# LED.net
KiCad netlist of a schematic drawn in EasyEDA
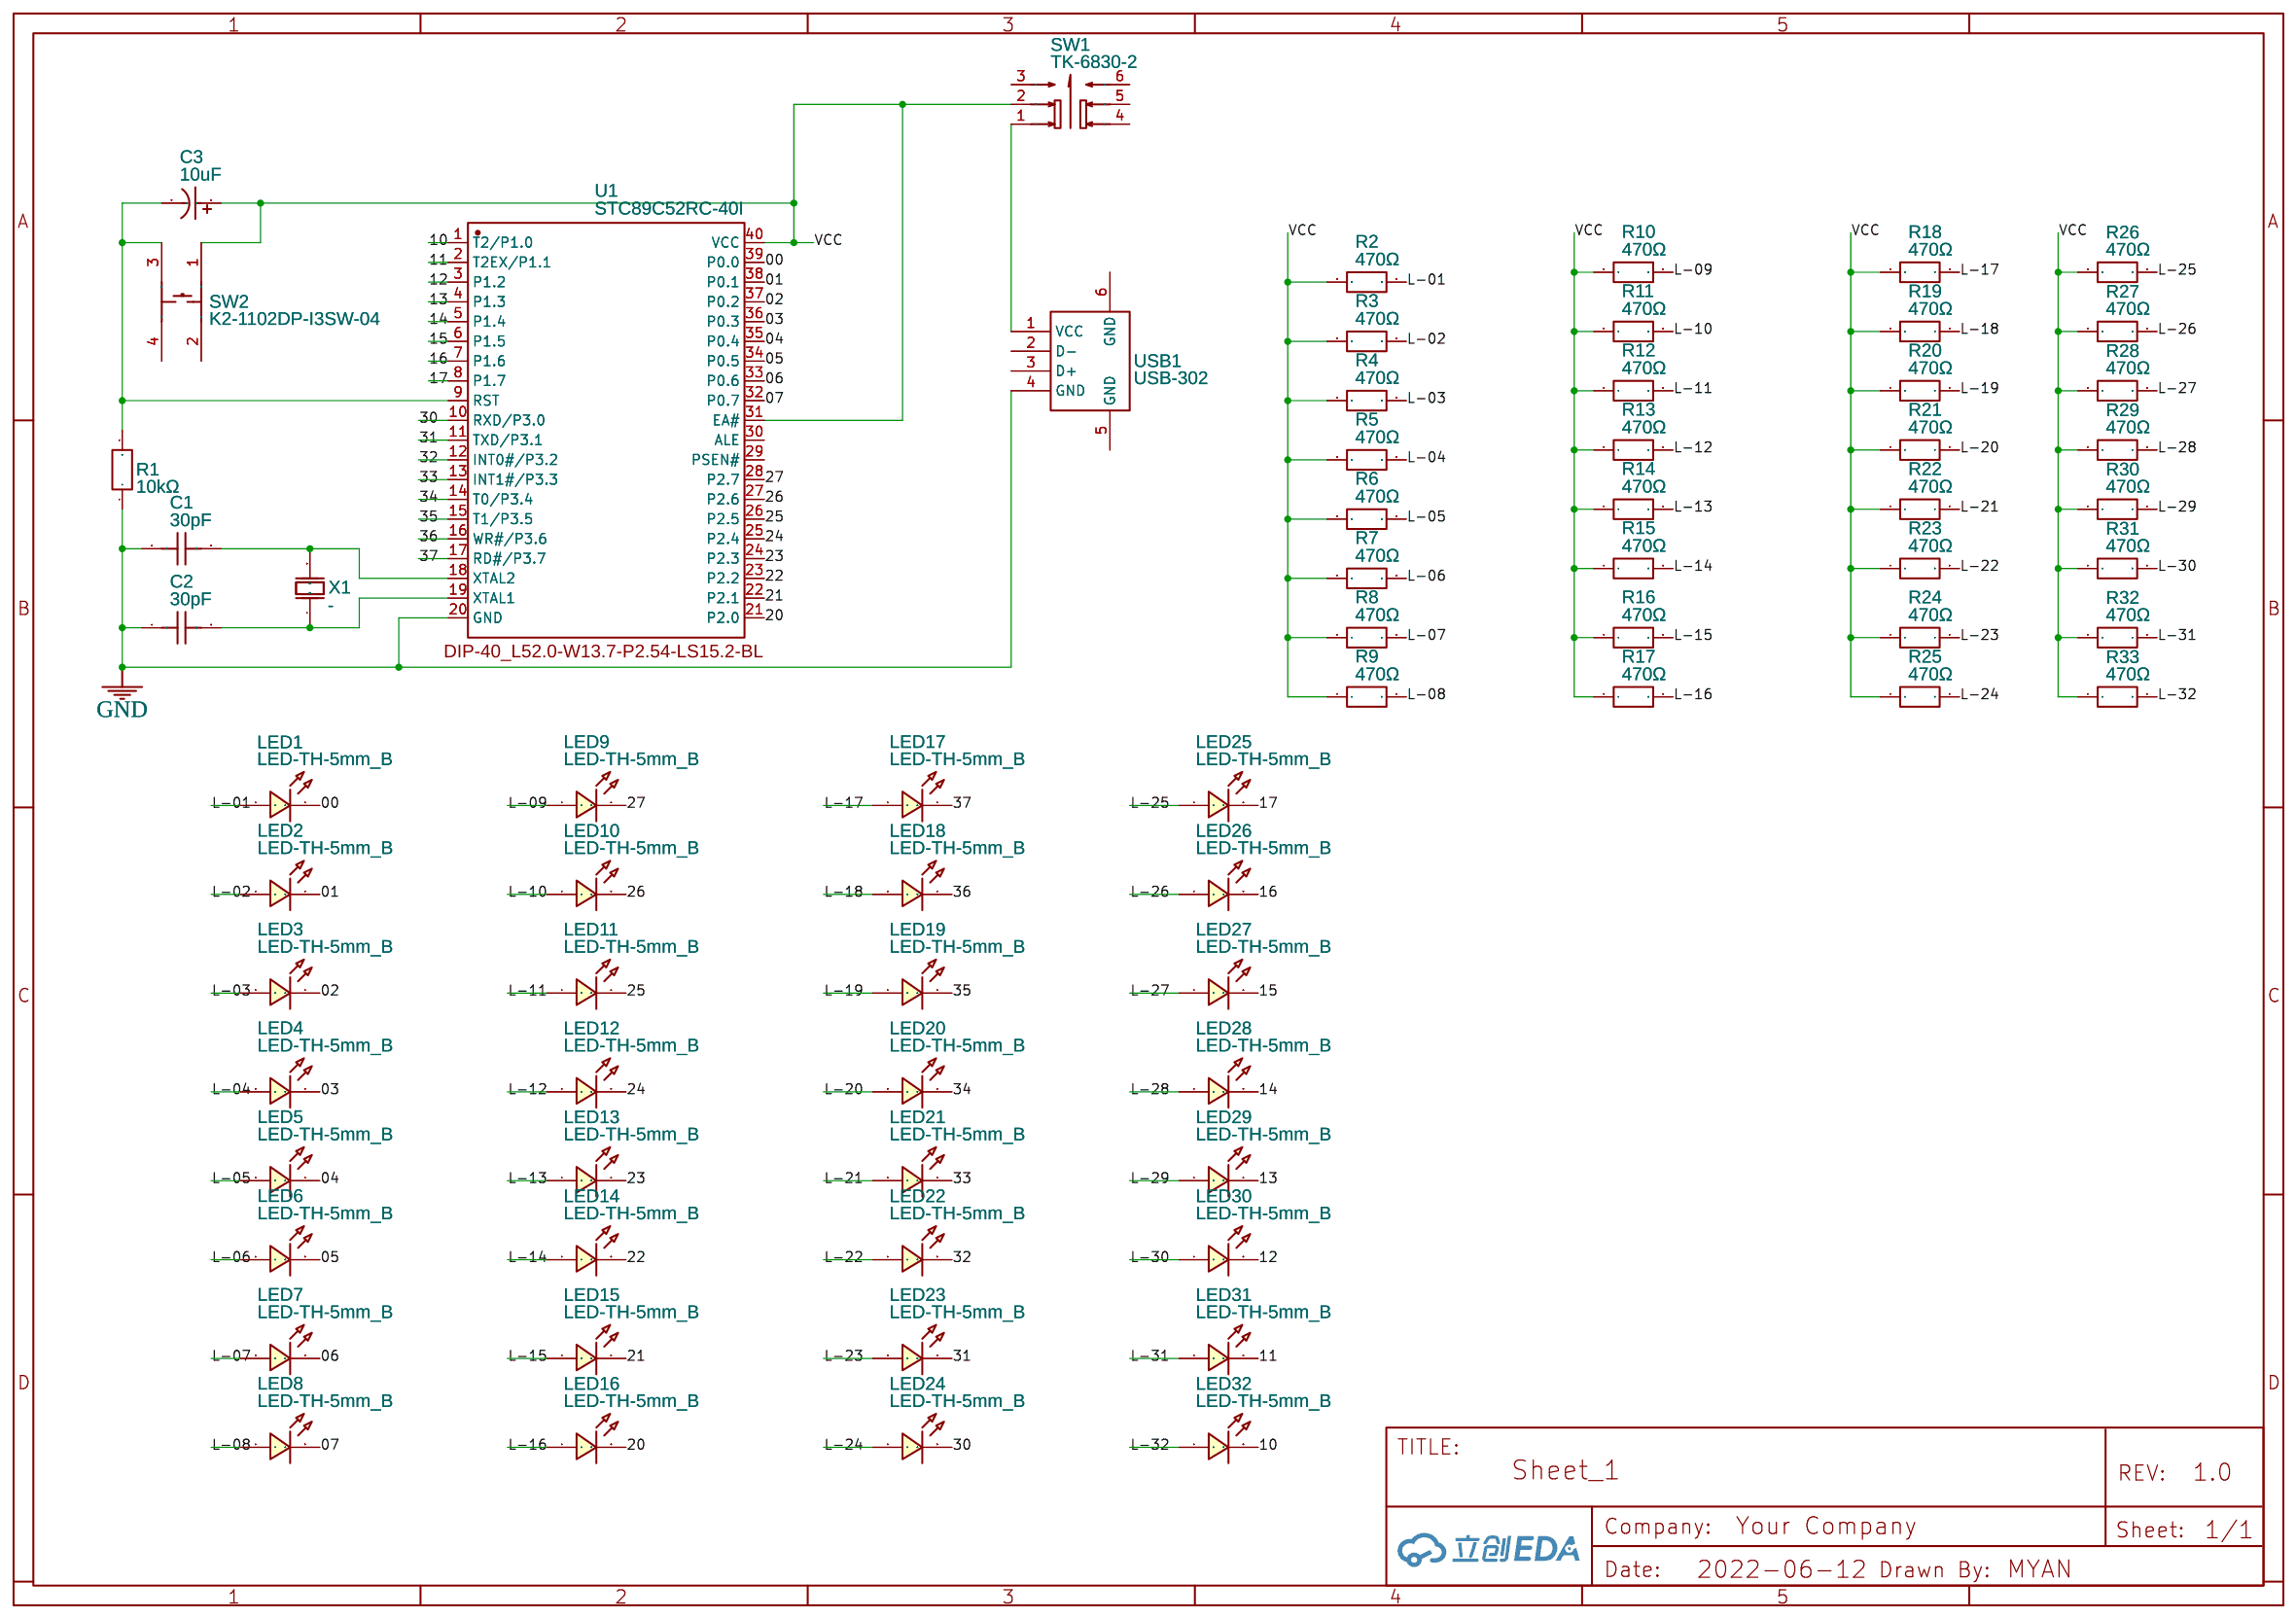
[diagram p0: schematic sheet]

(export (version "E")
  (design (tool "Eeschema 10.0.6"))
  (components
    (comp (ref "C1")
      (value "30pF")
      (fields
        (field (name "BOM_Manufacturer Part") "S07S1E330KN0B0S0N0")
        (field (name "BOM_Supplier Part") "C260735")
      )
      (libsource (lib "") (part "S07S1E330KN0B0S0N0"))
    )
    (comp (ref "C2")
      (value "30pF")
      (fields
        (field (name "BOM_Manufacturer Part") "S07S1E330KN0B0S0N0")
        (field (name "BOM_Supplier Part") "C260735")
      )
      (libsource (lib "") (part "S07S1E330KN0B0S0N0"))
    )
    (comp (ref "C3")
      (value "10uF")
      (fields (field (name "BOM_Manufacturer Part") "10uf/100V") (field (name "BOM_Supplier Part") "C2029"))
      (libsource (lib "") (part "10uf/100V"))
    )
    (comp (ref "LED1") (value "LED-TH-5mm_B") (libsource (lib "") (part "LED-TH-5mm_B")))
    (comp (ref "LED2") (value "LED-TH-5mm_B") (libsource (lib "") (part "LED-TH-5mm_B")))
    (comp (ref "LED3") (value "LED-TH-5mm_B") (libsource (lib "") (part "LED-TH-5mm_B")))
    (comp (ref "LED4") (value "LED-TH-5mm_B") (libsource (lib "") (part "LED-TH-5mm_B")))
    (comp (ref "LED5") (value "LED-TH-5mm_B") (libsource (lib "") (part "LED-TH-5mm_B")))
    (comp (ref "LED6") (value "LED-TH-5mm_B") (libsource (lib "") (part "LED-TH-5mm_B")))
    (comp (ref "LED7") (value "LED-TH-5mm_B") (libsource (lib "") (part "LED-TH-5mm_B")))
    (comp (ref "LED8") (value "LED-TH-5mm_B") (libsource (lib "") (part "LED-TH-5mm_B")))
    (comp (ref "LED9") (value "LED-TH-5mm_B") (libsource (lib "") (part "LED-TH-5mm_B")))
    (comp (ref "LED10") (value "LED-TH-5mm_B") (libsource (lib "") (part "LED-TH-5mm_B")))
    (comp (ref "LED11") (value "LED-TH-5mm_B") (libsource (lib "") (part "LED-TH-5mm_B")))
    (comp (ref "LED12") (value "LED-TH-5mm_B") (libsource (lib "") (part "LED-TH-5mm_B")))
    (comp (ref "LED13") (value "LED-TH-5mm_B") (libsource (lib "") (part "LED-TH-5mm_B")))
    (comp (ref "LED14") (value "LED-TH-5mm_B") (libsource (lib "") (part "LED-TH-5mm_B")))
    (comp (ref "LED15") (value "LED-TH-5mm_B") (libsource (lib "") (part "LED-TH-5mm_B")))
    (comp (ref "LED16") (value "LED-TH-5mm_B") (libsource (lib "") (part "LED-TH-5mm_B")))
    (comp (ref "LED17") (value "LED-TH-5mm_B") (libsource (lib "") (part "LED-TH-5mm_B")))
    (comp (ref "LED18") (value "LED-TH-5mm_B") (libsource (lib "") (part "LED-TH-5mm_B")))
    (comp (ref "LED19") (value "LED-TH-5mm_B") (libsource (lib "") (part "LED-TH-5mm_B")))
    (comp (ref "LED20") (value "LED-TH-5mm_B") (libsource (lib "") (part "LED-TH-5mm_B")))
    (comp (ref "LED21") (value "LED-TH-5mm_B") (libsource (lib "") (part "LED-TH-5mm_B")))
    (comp (ref "LED22") (value "LED-TH-5mm_B") (libsource (lib "") (part "LED-TH-5mm_B")))
    (comp (ref "LED23") (value "LED-TH-5mm_B") (libsource (lib "") (part "LED-TH-5mm_B")))
    (comp (ref "LED24") (value "LED-TH-5mm_B") (libsource (lib "") (part "LED-TH-5mm_B")))
    (comp (ref "LED25") (value "LED-TH-5mm_B") (libsource (lib "") (part "LED-TH-5mm_B")))
    (comp (ref "LED26") (value "LED-TH-5mm_B") (libsource (lib "") (part "LED-TH-5mm_B")))
    (comp (ref "LED27") (value "LED-TH-5mm_B") (libsource (lib "") (part "LED-TH-5mm_B")))
    (comp (ref "LED28") (value "LED-TH-5mm_B") (libsource (lib "") (part "LED-TH-5mm_B")))
    (comp (ref "LED29") (value "LED-TH-5mm_B") (libsource (lib "") (part "LED-TH-5mm_B")))
    (comp (ref "LED30") (value "LED-TH-5mm_B") (libsource (lib "") (part "LED-TH-5mm_B")))
    (comp (ref "LED31") (value "LED-TH-5mm_B") (libsource (lib "") (part "LED-TH-5mm_B")))
    (comp (ref "LED32") (value "LED-TH-5mm_B") (libsource (lib "") (part "LED-TH-5mm_B")))
    (comp (ref "R1")
      (value "10kΩ")
      (fields
        (field (name "BOM_Manufacturer Part") "MF3WS-10KΩ±1%T")
        (field (name "BOM_Supplier Part") "C714189")
      )
      (libsource (lib "") (part "MF3WS-10KΩ±1%T"))
    )
    (comp (ref "R2")
      (value "470Ω")
      (fields
        (field (name "BOM_Manufacturer Part") "MF1/2W-470Ω±1%T52")
        (field (name "BOM_Supplier Part") "C714066")
      )
      (libsource (lib "") (part "MF1/2W-470Ω±1%T52"))
    )
    (comp (ref "R3")
      (value "470Ω")
      (fields
        (field (name "BOM_Manufacturer Part") "MF1/2W-470Ω±1%T52")
        (field (name "BOM_Supplier Part") "C714066")
      )
      (libsource (lib "") (part "MF1/2W-470Ω±1%T52"))
    )
    (comp (ref "R4")
      (value "470Ω")
      (fields
        (field (name "BOM_Manufacturer Part") "MF1/2W-470Ω±1%T52")
        (field (name "BOM_Supplier Part") "C714066")
      )
      (libsource (lib "") (part "MF1/2W-470Ω±1%T52"))
    )
    (comp (ref "R5")
      (value "470Ω")
      (fields
        (field (name "BOM_Manufacturer Part") "MF1/2W-470Ω±1%T52")
        (field (name "BOM_Supplier Part") "C714066")
      )
      (libsource (lib "") (part "MF1/2W-470Ω±1%T52"))
    )
    (comp (ref "R6")
      (value "470Ω")
      (fields
        (field (name "BOM_Manufacturer Part") "MF1/2W-470Ω±1%T52")
        (field (name "BOM_Supplier Part") "C714066")
      )
      (libsource (lib "") (part "MF1/2W-470Ω±1%T52"))
    )
    (comp (ref "R7")
      (value "470Ω")
      (fields
        (field (name "BOM_Manufacturer Part") "MF1/2W-470Ω±1%T52")
        (field (name "BOM_Supplier Part") "C714066")
      )
      (libsource (lib "") (part "MF1/2W-470Ω±1%T52"))
    )
    (comp (ref "R8")
      (value "470Ω")
      (fields
        (field (name "BOM_Manufacturer Part") "MF1/2W-470Ω±1%T52")
        (field (name "BOM_Supplier Part") "C714066")
      )
      (libsource (lib "") (part "MF1/2W-470Ω±1%T52"))
    )
    (comp (ref "R9")
      (value "470Ω")
      (fields
        (field (name "BOM_Manufacturer Part") "MF1/2W-470Ω±1%T52")
        (field (name "BOM_Supplier Part") "C714066")
      )
      (libsource (lib "") (part "MF1/2W-470Ω±1%T52"))
    )
    (comp (ref "R10")
      (value "470Ω")
      (fields
        (field (name "BOM_Manufacturer Part") "MF1/2W-470Ω±1%T52")
        (field (name "BOM_Supplier Part") "C714066")
      )
      (libsource (lib "") (part "MF1/2W-470Ω±1%T52"))
    )
    (comp (ref "R11")
      (value "470Ω")
      (fields
        (field (name "BOM_Manufacturer Part") "MF1/2W-470Ω±1%T52")
        (field (name "BOM_Supplier Part") "C714066")
      )
      (libsource (lib "") (part "MF1/2W-470Ω±1%T52"))
    )
    (comp (ref "R12")
      (value "470Ω")
      (fields
        (field (name "BOM_Manufacturer Part") "MF1/2W-470Ω±1%T52")
        (field (name "BOM_Supplier Part") "C714066")
      )
      (libsource (lib "") (part "MF1/2W-470Ω±1%T52"))
    )
    (comp (ref "R13")
      (value "470Ω")
      (fields
        (field (name "BOM_Manufacturer Part") "MF1/2W-470Ω±1%T52")
        (field (name "BOM_Supplier Part") "C714066")
      )
      (libsource (lib "") (part "MF1/2W-470Ω±1%T52"))
    )
    (comp (ref "R14")
      (value "470Ω")
      (fields
        (field (name "BOM_Manufacturer Part") "MF1/2W-470Ω±1%T52")
        (field (name "BOM_Supplier Part") "C714066")
      )
      (libsource (lib "") (part "MF1/2W-470Ω±1%T52"))
    )
    (comp (ref "R15")
      (value "470Ω")
      (fields
        (field (name "BOM_Manufacturer Part") "MF1/2W-470Ω±1%T52")
        (field (name "BOM_Supplier Part") "C714066")
      )
      (libsource (lib "") (part "MF1/2W-470Ω±1%T52"))
    )
    (comp (ref "R16")
      (value "470Ω")
      (fields
        (field (name "BOM_Manufacturer Part") "MF1/2W-470Ω±1%T52")
        (field (name "BOM_Supplier Part") "C714066")
      )
      (libsource (lib "") (part "MF1/2W-470Ω±1%T52"))
    )
    (comp (ref "R17")
      (value "470Ω")
      (fields
        (field (name "BOM_Manufacturer Part") "MF1/2W-470Ω±1%T52")
        (field (name "BOM_Supplier Part") "C714066")
      )
      (libsource (lib "") (part "MF1/2W-470Ω±1%T52"))
    )
    (comp (ref "R18")
      (value "470Ω")
      (fields
        (field (name "BOM_Manufacturer Part") "MF1/2W-470Ω±1%T52")
        (field (name "BOM_Supplier Part") "C714066")
      )
      (libsource (lib "") (part "MF1/2W-470Ω±1%T52"))
    )
    (comp (ref "R19")
      (value "470Ω")
      (fields
        (field (name "BOM_Manufacturer Part") "MF1/2W-470Ω±1%T52")
        (field (name "BOM_Supplier Part") "C714066")
      )
      (libsource (lib "") (part "MF1/2W-470Ω±1%T52"))
    )
    (comp (ref "R20")
      (value "470Ω")
      (fields
        (field (name "BOM_Manufacturer Part") "MF1/2W-470Ω±1%T52")
        (field (name "BOM_Supplier Part") "C714066")
      )
      (libsource (lib "") (part "MF1/2W-470Ω±1%T52"))
    )
    (comp (ref "R21")
      (value "470Ω")
      (fields
        (field (name "BOM_Manufacturer Part") "MF1/2W-470Ω±1%T52")
        (field (name "BOM_Supplier Part") "C714066")
      )
      (libsource (lib "") (part "MF1/2W-470Ω±1%T52"))
    )
    (comp (ref "R22")
      (value "470Ω")
      (fields
        (field (name "BOM_Manufacturer Part") "MF1/2W-470Ω±1%T52")
        (field (name "BOM_Supplier Part") "C714066")
      )
      (libsource (lib "") (part "MF1/2W-470Ω±1%T52"))
    )
    (comp (ref "R23")
      (value "470Ω")
      (fields
        (field (name "BOM_Manufacturer Part") "MF1/2W-470Ω±1%T52")
        (field (name "BOM_Supplier Part") "C714066")
      )
      (libsource (lib "") (part "MF1/2W-470Ω±1%T52"))
    )
    (comp (ref "R24")
      (value "470Ω")
      (fields
        (field (name "BOM_Manufacturer Part") "MF1/2W-470Ω±1%T52")
        (field (name "BOM_Supplier Part") "C714066")
      )
      (libsource (lib "") (part "MF1/2W-470Ω±1%T52"))
    )
    (comp (ref "R25")
      (value "470Ω")
      (fields
        (field (name "BOM_Manufacturer Part") "MF1/2W-470Ω±1%T52")
        (field (name "BOM_Supplier Part") "C714066")
      )
      (libsource (lib "") (part "MF1/2W-470Ω±1%T52"))
    )
    (comp (ref "R26")
      (value "470Ω")
      (fields
        (field (name "BOM_Manufacturer Part") "MF1/2W-470Ω±1%T52")
        (field (name "BOM_Supplier Part") "C714066")
      )
      (libsource (lib "") (part "MF1/2W-470Ω±1%T52"))
    )
    (comp (ref "R27")
      (value "470Ω")
      (fields
        (field (name "BOM_Manufacturer Part") "MF1/2W-470Ω±1%T52")
        (field (name "BOM_Supplier Part") "C714066")
      )
      (libsource (lib "") (part "MF1/2W-470Ω±1%T52"))
    )
    (comp (ref "R28")
      (value "470Ω")
      (fields
        (field (name "BOM_Manufacturer Part") "MF1/2W-470Ω±1%T52")
        (field (name "BOM_Supplier Part") "C714066")
      )
      (libsource (lib "") (part "MF1/2W-470Ω±1%T52"))
    )
    (comp (ref "R29")
      (value "470Ω")
      (fields
        (field (name "BOM_Manufacturer Part") "MF1/2W-470Ω±1%T52")
        (field (name "BOM_Supplier Part") "C714066")
      )
      (libsource (lib "") (part "MF1/2W-470Ω±1%T52"))
    )
    (comp (ref "R30")
      (value "470Ω")
      (fields
        (field (name "BOM_Manufacturer Part") "MF1/2W-470Ω±1%T52")
        (field (name "BOM_Supplier Part") "C714066")
      )
      (libsource (lib "") (part "MF1/2W-470Ω±1%T52"))
    )
    (comp (ref "R31")
      (value "470Ω")
      (fields
        (field (name "BOM_Manufacturer Part") "MF1/2W-470Ω±1%T52")
        (field (name "BOM_Supplier Part") "C714066")
      )
      (libsource (lib "") (part "MF1/2W-470Ω±1%T52"))
    )
    (comp (ref "R32")
      (value "470Ω")
      (fields
        (field (name "BOM_Manufacturer Part") "MF1/2W-470Ω±1%T52")
        (field (name "BOM_Supplier Part") "C714066")
      )
      (libsource (lib "") (part "MF1/2W-470Ω±1%T52"))
    )
    (comp (ref "R33")
      (value "470Ω")
      (fields
        (field (name "BOM_Manufacturer Part") "MF1/2W-470Ω±1%T52")
        (field (name "BOM_Supplier Part") "C714066")
      )
      (libsource (lib "") (part "MF1/2W-470Ω±1%T52"))
    )
    (comp (ref "SW1")
      (value "TK-6830-2")
      (fields (field (name "BOM_Supplier Part") "C528789"))
      (libsource (lib "") (part "TK-6830-2"))
    )
    (comp (ref "SW2")
      (value "K2-1102DP-I3SW-04")
      (fields (field (name "BOM_Supplier Part") "C2685962"))
      (libsource (lib "") (part "K2-1102DP-I3SW-04"))
    )
    (comp (ref "U1")
      (value "STC89C52RC-40I")
      (fields (field (name "BOM_Supplier Part") "C14022"))
      (libsource (lib "") (part "STC89C52RC-40I"))
    )
    (comp (ref "USB1")
      (value "USB-302")
      (fields (field (name "BOM_Supplier Part") "C112456"))
      (libsource (lib "") (part "USB-302"))
    )
    (comp (ref "X1")
      (value "-")
      (fields
        (field (name "BOM_Manufacturer Part") "ESA11.0592F20M25F")
        (field (name "BOM_Supplier Part") "C353687")
      )
      (libsource (lib "") (part "ESA11.0592F20M25F"))
    )
  )
  (nets
    (net (code "1") (name "/00") (class "Default")
      (node (ref "LED1") (pin "2") (pinfunction "2_2") (pintype "unspecified"))
      (node (ref "U1") (pin "39") (pinfunction "P0.0_39") (pintype "unspecified"))
    )
    (net (code "2") (name "/01") (class "Default")
      (node (ref "LED2") (pin "2") (pinfunction "2_2") (pintype "unspecified"))
      (node (ref "U1") (pin "38") (pinfunction "P0.1_38") (pintype "unspecified"))
    )
    (net (code "3") (name "/02") (class "Default")
      (node (ref "LED3") (pin "2") (pinfunction "2_2") (pintype "unspecified"))
      (node (ref "U1") (pin "37") (pinfunction "P0.2_37") (pintype "unspecified"))
    )
    (net (code "4") (name "/03") (class "Default")
      (node (ref "LED4") (pin "2") (pinfunction "2_2") (pintype "unspecified"))
      (node (ref "U1") (pin "36") (pinfunction "P0.3_36") (pintype "unspecified"))
    )
    (net (code "5") (name "/04") (class "Default")
      (node (ref "LED5") (pin "2") (pinfunction "2_2") (pintype "unspecified"))
      (node (ref "U1") (pin "35") (pinfunction "P0.4_35") (pintype "unspecified"))
    )
    (net (code "6") (name "/05") (class "Default")
      (node (ref "LED6") (pin "2") (pinfunction "2_2") (pintype "unspecified"))
      (node (ref "U1") (pin "34") (pinfunction "P0.5_34") (pintype "unspecified"))
    )
    (net (code "7") (name "/06") (class "Default")
      (node (ref "LED7") (pin "2") (pinfunction "2_2") (pintype "unspecified"))
      (node (ref "U1") (pin "33") (pinfunction "P0.6_33") (pintype "unspecified"))
    )
    (net (code "8") (name "/07") (class "Default")
      (node (ref "LED8") (pin "2") (pinfunction "2_2") (pintype "unspecified"))
      (node (ref "U1") (pin "32") (pinfunction "P0.7_32") (pintype "unspecified"))
    )
    (net (code "9") (name "/10") (class "Default")
      (node (ref "LED32") (pin "2") (pinfunction "2_2") (pintype "unspecified"))
      (node (ref "U1") (pin "1") (pinfunction "T2/P1.0_1") (pintype "unspecified"))
    )
    (net (code "10") (name "/11") (class "Default")
      (node (ref "LED31") (pin "2") (pinfunction "2_2") (pintype "unspecified"))
      (node (ref "U1") (pin "2") (pinfunction "T2EX/P1.1_2") (pintype "unspecified"))
    )
    (net (code "11") (name "/12") (class "Default")
      (node (ref "LED30") (pin "2") (pinfunction "2_2") (pintype "unspecified"))
      (node (ref "U1") (pin "3") (pinfunction "P1.2_3") (pintype "unspecified"))
    )
    (net (code "12") (name "/13") (class "Default")
      (node (ref "LED29") (pin "2") (pinfunction "2_2") (pintype "unspecified"))
      (node (ref "U1") (pin "4") (pinfunction "P1.3_4") (pintype "unspecified"))
    )
    (net (code "13") (name "/14") (class "Default")
      (node (ref "LED28") (pin "2") (pinfunction "2_2") (pintype "unspecified"))
      (node (ref "U1") (pin "5") (pinfunction "P1.4_5") (pintype "unspecified"))
    )
    (net (code "14") (name "/15") (class "Default")
      (node (ref "LED27") (pin "2") (pinfunction "2_2") (pintype "unspecified"))
      (node (ref "U1") (pin "6") (pinfunction "P1.5_6") (pintype "unspecified"))
    )
    (net (code "15") (name "/16") (class "Default")
      (node (ref "LED26") (pin "2") (pinfunction "2_2") (pintype "unspecified"))
      (node (ref "U1") (pin "7") (pinfunction "P1.6_7") (pintype "unspecified"))
    )
    (net (code "16") (name "/17") (class "Default")
      (node (ref "LED25") (pin "2") (pinfunction "2_2") (pintype "unspecified"))
      (node (ref "U1") (pin "8") (pinfunction "P1.7_8") (pintype "unspecified"))
    )
    (net (code "17") (name "/20") (class "Default")
      (node (ref "LED16") (pin "2") (pinfunction "2_2") (pintype "unspecified"))
      (node (ref "U1") (pin "21") (pinfunction "P2.0_21") (pintype "unspecified"))
    )
    (net (code "18") (name "/21") (class "Default")
      (node (ref "LED15") (pin "2") (pinfunction "2_2") (pintype "unspecified"))
      (node (ref "U1") (pin "22") (pinfunction "P2.1_22") (pintype "unspecified"))
    )
    (net (code "19") (name "/22") (class "Default")
      (node (ref "LED14") (pin "2") (pinfunction "2_2") (pintype "unspecified"))
      (node (ref "U1") (pin "23") (pinfunction "P2.2_23") (pintype "unspecified"))
    )
    (net (code "20") (name "/23") (class "Default")
      (node (ref "LED13") (pin "2") (pinfunction "2_2") (pintype "unspecified"))
      (node (ref "U1") (pin "24") (pinfunction "P2.3_24") (pintype "unspecified"))
    )
    (net (code "21") (name "/24") (class "Default")
      (node (ref "LED12") (pin "2") (pinfunction "2_2") (pintype "unspecified"))
      (node (ref "U1") (pin "25") (pinfunction "P2.4_25") (pintype "unspecified"))
    )
    (net (code "22") (name "/25") (class "Default")
      (node (ref "LED11") (pin "2") (pinfunction "2_2") (pintype "unspecified"))
      (node (ref "U1") (pin "26") (pinfunction "P2.5_26") (pintype "unspecified"))
    )
    (net (code "23") (name "/26") (class "Default")
      (node (ref "LED10") (pin "2") (pinfunction "2_2") (pintype "unspecified"))
      (node (ref "U1") (pin "27") (pinfunction "P2.6_27") (pintype "unspecified"))
    )
    (net (code "24") (name "/27") (class "Default")
      (node (ref "LED9") (pin "2") (pinfunction "2_2") (pintype "unspecified"))
      (node (ref "U1") (pin "28") (pinfunction "P2.7_28") (pintype "unspecified"))
    )
    (net (code "25") (name "/30") (class "Default")
      (node (ref "LED24") (pin "2") (pinfunction "2_2") (pintype "unspecified"))
      (node (ref "U1") (pin "10") (pinfunction "RXD/P3.0_10") (pintype "unspecified"))
    )
    (net (code "26") (name "/31") (class "Default")
      (node (ref "LED23") (pin "2") (pinfunction "2_2") (pintype "unspecified"))
      (node (ref "U1") (pin "11") (pinfunction "TXD/P3.1_11") (pintype "unspecified"))
    )
    (net (code "27") (name "/32") (class "Default")
      (node (ref "LED22") (pin "2") (pinfunction "2_2") (pintype "unspecified"))
      (node (ref "U1") (pin "12") (pinfunction "INT0#/P3.2_12") (pintype "unspecified"))
    )
    (net (code "28") (name "/33") (class "Default")
      (node (ref "LED21") (pin "2") (pinfunction "2_2") (pintype "unspecified"))
      (node (ref "U1") (pin "13") (pinfunction "INT1#/P3.3_13") (pintype "unspecified"))
    )
    (net (code "29") (name "/34") (class "Default")
      (node (ref "LED20") (pin "2") (pinfunction "2_2") (pintype "unspecified"))
      (node (ref "U1") (pin "14") (pinfunction "T0/P3.4_14") (pintype "unspecified"))
    )
    (net (code "30") (name "/35") (class "Default")
      (node (ref "LED19") (pin "2") (pinfunction "2_2") (pintype "unspecified"))
      (node (ref "U1") (pin "15") (pinfunction "T1/P3.5_15") (pintype "unspecified"))
    )
    (net (code "31") (name "/36") (class "Default")
      (node (ref "LED18") (pin "2") (pinfunction "2_2") (pintype "unspecified"))
      (node (ref "U1") (pin "16") (pinfunction "WR#/P3.6_16") (pintype "unspecified"))
    )
    (net (code "32") (name "/37") (class "Default")
      (node (ref "LED17") (pin "2") (pinfunction "2_2") (pintype "unspecified"))
      (node (ref "U1") (pin "17") (pinfunction "RD#/P3.7_17") (pintype "unspecified"))
    )
    (net (code "33") (name "/L-01") (class "Default")
      (node (ref "LED1") (pin "1") (pinfunction "1_1") (pintype "unspecified"))
      (node (ref "R2") (pin "2") (pinfunction "2_2") (pintype "unspecified"))
    )
    (net (code "34") (name "/L-02") (class "Default")
      (node (ref "LED2") (pin "1") (pinfunction "1_1") (pintype "unspecified"))
      (node (ref "R3") (pin "2") (pinfunction "2_2") (pintype "unspecified"))
    )
    (net (code "35") (name "/L-03") (class "Default")
      (node (ref "LED3") (pin "1") (pinfunction "1_1") (pintype "unspecified"))
      (node (ref "R4") (pin "2") (pinfunction "2_2") (pintype "unspecified"))
    )
    (net (code "36") (name "/L-04") (class "Default")
      (node (ref "LED4") (pin "1") (pinfunction "1_1") (pintype "unspecified"))
      (node (ref "R5") (pin "2") (pinfunction "2_2") (pintype "unspecified"))
    )
    (net (code "37") (name "/L-05") (class "Default")
      (node (ref "LED5") (pin "1") (pinfunction "1_1") (pintype "unspecified"))
      (node (ref "R6") (pin "2") (pinfunction "2_2") (pintype "unspecified"))
    )
    (net (code "38") (name "/L-06") (class "Default")
      (node (ref "LED6") (pin "1") (pinfunction "1_1") (pintype "unspecified"))
      (node (ref "R7") (pin "2") (pinfunction "2_2") (pintype "unspecified"))
    )
    (net (code "39") (name "/L-07") (class "Default")
      (node (ref "LED7") (pin "1") (pinfunction "1_1") (pintype "unspecified"))
      (node (ref "R8") (pin "2") (pinfunction "2_2") (pintype "unspecified"))
    )
    (net (code "40") (name "/L-08") (class "Default")
      (node (ref "LED8") (pin "1") (pinfunction "1_1") (pintype "unspecified"))
      (node (ref "R9") (pin "2") (pinfunction "2_2") (pintype "unspecified"))
    )
    (net (code "41") (name "/L-09") (class "Default")
      (node (ref "LED9") (pin "1") (pinfunction "1_1") (pintype "unspecified"))
      (node (ref "R10") (pin "2") (pinfunction "2_2") (pintype "unspecified"))
    )
    (net (code "42") (name "/L-10") (class "Default")
      (node (ref "LED10") (pin "1") (pinfunction "1_1") (pintype "unspecified"))
      (node (ref "R11") (pin "2") (pinfunction "2_2") (pintype "unspecified"))
    )
    (net (code "43") (name "/L-11") (class "Default")
      (node (ref "LED11") (pin "1") (pinfunction "1_1") (pintype "unspecified"))
      (node (ref "R12") (pin "2") (pinfunction "2_2") (pintype "unspecified"))
    )
    (net (code "44") (name "/L-12") (class "Default")
      (node (ref "LED12") (pin "1") (pinfunction "1_1") (pintype "unspecified"))
      (node (ref "R13") (pin "2") (pinfunction "2_2") (pintype "unspecified"))
    )
    (net (code "45") (name "/L-13") (class "Default")
      (node (ref "LED13") (pin "1") (pinfunction "1_1") (pintype "unspecified"))
      (node (ref "R14") (pin "2") (pinfunction "2_2") (pintype "unspecified"))
    )
    (net (code "46") (name "/L-14") (class "Default")
      (node (ref "LED14") (pin "1") (pinfunction "1_1") (pintype "unspecified"))
      (node (ref "R15") (pin "2") (pinfunction "2_2") (pintype "unspecified"))
    )
    (net (code "47") (name "/L-15") (class "Default")
      (node (ref "LED15") (pin "1") (pinfunction "1_1") (pintype "unspecified"))
      (node (ref "R16") (pin "2") (pinfunction "2_2") (pintype "unspecified"))
    )
    (net (code "48") (name "/L-16") (class "Default")
      (node (ref "LED16") (pin "1") (pinfunction "1_1") (pintype "unspecified"))
      (node (ref "R17") (pin "2") (pinfunction "2_2") (pintype "unspecified"))
    )
    (net (code "49") (name "/L-17") (class "Default")
      (node (ref "LED17") (pin "1") (pinfunction "1_1") (pintype "unspecified"))
      (node (ref "R18") (pin "2") (pinfunction "2_2") (pintype "unspecified"))
    )
    (net (code "50") (name "/L-18") (class "Default")
      (node (ref "LED18") (pin "1") (pinfunction "1_1") (pintype "unspecified"))
      (node (ref "R19") (pin "2") (pinfunction "2_2") (pintype "unspecified"))
    )
    (net (code "51") (name "/L-19") (class "Default")
      (node (ref "LED19") (pin "1") (pinfunction "1_1") (pintype "unspecified"))
      (node (ref "R20") (pin "2") (pinfunction "2_2") (pintype "unspecified"))
    )
    (net (code "52") (name "/L-20") (class "Default")
      (node (ref "LED20") (pin "1") (pinfunction "1_1") (pintype "unspecified"))
      (node (ref "R21") (pin "2") (pinfunction "2_2") (pintype "unspecified"))
    )
    (net (code "53") (name "/L-21") (class "Default")
      (node (ref "LED21") (pin "1") (pinfunction "1_1") (pintype "unspecified"))
      (node (ref "R22") (pin "2") (pinfunction "2_2") (pintype "unspecified"))
    )
    (net (code "54") (name "/L-22") (class "Default")
      (node (ref "LED22") (pin "1") (pinfunction "1_1") (pintype "unspecified"))
      (node (ref "R23") (pin "2") (pinfunction "2_2") (pintype "unspecified"))
    )
    (net (code "55") (name "/L-23") (class "Default")
      (node (ref "LED23") (pin "1") (pinfunction "1_1") (pintype "unspecified"))
      (node (ref "R24") (pin "2") (pinfunction "2_2") (pintype "unspecified"))
    )
    (net (code "56") (name "/L-24") (class "Default")
      (node (ref "LED24") (pin "1") (pinfunction "1_1") (pintype "unspecified"))
      (node (ref "R25") (pin "2") (pinfunction "2_2") (pintype "unspecified"))
    )
    (net (code "57") (name "/L-25") (class "Default")
      (node (ref "LED25") (pin "1") (pinfunction "1_1") (pintype "unspecified"))
      (node (ref "R26") (pin "2") (pinfunction "2_2") (pintype "unspecified"))
    )
    (net (code "58") (name "/L-26") (class "Default")
      (node (ref "LED26") (pin "1") (pinfunction "1_1") (pintype "unspecified"))
      (node (ref "R27") (pin "2") (pinfunction "2_2") (pintype "unspecified"))
    )
    (net (code "59") (name "/L-27") (class "Default")
      (node (ref "LED27") (pin "1") (pinfunction "1_1") (pintype "unspecified"))
      (node (ref "R28") (pin "2") (pinfunction "2_2") (pintype "unspecified"))
    )
    (net (code "60") (name "/L-28") (class "Default")
      (node (ref "LED28") (pin "1") (pinfunction "1_1") (pintype "unspecified"))
      (node (ref "R29") (pin "2") (pinfunction "2_2") (pintype "unspecified"))
    )
    (net (code "61") (name "/L-29") (class "Default")
      (node (ref "LED29") (pin "1") (pinfunction "1_1") (pintype "unspecified"))
      (node (ref "R30") (pin "2") (pinfunction "2_2") (pintype "unspecified"))
    )
    (net (code "62") (name "/L-30") (class "Default")
      (node (ref "LED30") (pin "1") (pinfunction "1_1") (pintype "unspecified"))
      (node (ref "R31") (pin "2") (pinfunction "2_2") (pintype "unspecified"))
    )
    (net (code "63") (name "/L-31") (class "Default")
      (node (ref "LED31") (pin "1") (pinfunction "1_1") (pintype "unspecified"))
      (node (ref "R32") (pin "2") (pinfunction "2_2") (pintype "unspecified"))
    )
    (net (code "64") (name "/L-32") (class "Default")
      (node (ref "LED32") (pin "1") (pinfunction "1_1") (pintype "unspecified"))
      (node (ref "R33") (pin "2") (pinfunction "2_2") (pintype "unspecified"))
    )
    (net (code "65") (name "/VCC") (class "Default")
      (node (ref "C3") (pin "1") (pinfunction "1_1") (pintype "input"))
      (node (ref "R10") (pin "1") (pinfunction "1_1") (pintype "unspecified"))
      (node (ref "R11") (pin "1") (pinfunction "1_1") (pintype "unspecified"))
      (node (ref "R12") (pin "1") (pinfunction "1_1") (pintype "unspecified"))
      (node (ref "R13") (pin "1") (pinfunction "1_1") (pintype "unspecified"))
      (node (ref "R14") (pin "1") (pinfunction "1_1") (pintype "unspecified"))
      (node (ref "R15") (pin "1") (pinfunction "1_1") (pintype "unspecified"))
      (node (ref "R16") (pin "1") (pinfunction "1_1") (pintype "unspecified"))
      (node (ref "R17") (pin "1") (pinfunction "1_1") (pintype "unspecified"))
      (node (ref "R18") (pin "1") (pinfunction "1_1") (pintype "unspecified"))
      (node (ref "R19") (pin "1") (pinfunction "1_1") (pintype "unspecified"))
      (node (ref "R2") (pin "1") (pinfunction "1_1") (pintype "unspecified"))
      (node (ref "R20") (pin "1") (pinfunction "1_1") (pintype "unspecified"))
      (node (ref "R21") (pin "1") (pinfunction "1_1") (pintype "unspecified"))
      (node (ref "R22") (pin "1") (pinfunction "1_1") (pintype "unspecified"))
      (node (ref "R23") (pin "1") (pinfunction "1_1") (pintype "unspecified"))
      (node (ref "R24") (pin "1") (pinfunction "1_1") (pintype "unspecified"))
      (node (ref "R25") (pin "1") (pinfunction "1_1") (pintype "unspecified"))
      (node (ref "R26") (pin "1") (pinfunction "1_1") (pintype "unspecified"))
      (node (ref "R27") (pin "1") (pinfunction "1_1") (pintype "unspecified"))
      (node (ref "R28") (pin "1") (pinfunction "1_1") (pintype "unspecified"))
      (node (ref "R29") (pin "1") (pinfunction "1_1") (pintype "unspecified"))
      (node (ref "R3") (pin "1") (pinfunction "1_1") (pintype "unspecified"))
      (node (ref "R30") (pin "1") (pinfunction "1_1") (pintype "unspecified"))
      (node (ref "R31") (pin "1") (pinfunction "1_1") (pintype "unspecified"))
      (node (ref "R32") (pin "1") (pinfunction "1_1") (pintype "unspecified"))
      (node (ref "R33") (pin "1") (pinfunction "1_1") (pintype "unspecified"))
      (node (ref "R4") (pin "1") (pinfunction "1_1") (pintype "unspecified"))
      (node (ref "R5") (pin "1") (pinfunction "1_1") (pintype "unspecified"))
      (node (ref "R6") (pin "1") (pinfunction "1_1") (pintype "unspecified"))
      (node (ref "R7") (pin "1") (pinfunction "1_1") (pintype "unspecified"))
      (node (ref "R8") (pin "1") (pinfunction "1_1") (pintype "unspecified"))
      (node (ref "R9") (pin "1") (pinfunction "1_1") (pintype "unspecified"))
      (node (ref "SW1") (pin "2") (pinfunction "2_2") (pintype "unspecified"))
      (node (ref "SW2") (pin "1") (pinfunction "1_1") (pintype "unspecified"))
      (node (ref "U1") (pin "31") (pinfunction "EA#_31") (pintype "unspecified"))
      (node (ref "U1") (pin "40") (pinfunction "VCC_40") (pintype "unspecified"))
    )
    (net (code "66") (name "GND") (class "Default")
      (node (ref "C1") (pin "1") (pinfunction "1_1") (pintype "unspecified"))
      (node (ref "C2") (pin "1") (pinfunction "1_1") (pintype "unspecified"))
      (node (ref "R1") (pin "1") (pinfunction "1_1") (pintype "unspecified"))
      (node (ref "U1") (pin "20") (pinfunction "GND_20") (pintype "unspecified"))
      (node (ref "USB1") (pin "4") (pinfunction "GND_4") (pintype "unspecified"))
    )
    (net (code "67") (name "Net-(U1-RST)") (class "Default")
      (node (ref "C3") (pin "2") (pinfunction "2_2") (pintype "input"))
      (node (ref "R1") (pin "2") (pinfunction "2_2") (pintype "unspecified"))
      (node (ref "SW2") (pin "3") (pinfunction "3_3") (pintype "unspecified"))
      (node (ref "U1") (pin "9") (pinfunction "RST_9") (pintype "unspecified"))
    )
    (net (code "68") (name "Net-(U1-XTAL1)") (class "Default")
      (node (ref "C2") (pin "2") (pinfunction "2_2") (pintype "unspecified"))
      (node (ref "U1") (pin "19") (pinfunction "XTAL1_19") (pintype "unspecified"))
      (node (ref "X1") (pin "1") (pinfunction "OSC1_1") (pintype "input"))
    )
    (net (code "69") (name "Net-(U1-XTAL2)") (class "Default")
      (node (ref "C1") (pin "2") (pinfunction "2_2") (pintype "unspecified"))
      (node (ref "U1") (pin "18") (pinfunction "XTAL2_18") (pintype "unspecified"))
      (node (ref "X1") (pin "2") (pinfunction "OSC2_2") (pintype "input"))
    )
    (net (code "70") (name "Net-(USB1-VCC)") (class "Default")
      (node (ref "SW1") (pin "1") (pinfunction "1_1") (pintype "unspecified"))
      (node (ref "USB1") (pin "1") (pinfunction "VCC_1") (pintype "unspecified"))
    )
    (net (code "71") (name "unconnected-(SW1-Pad3)") (class "Default")
      (node (ref "SW1") (pin "3") (pinfunction "3_3") (pintype "unspecified"))
    )
    (net (code "72") (name "unconnected-(SW1-Pad4)") (class "Default")
      (node (ref "SW1") (pin "4") (pinfunction "4_4") (pintype "unspecified"))
    )
    (net (code "73") (name "unconnected-(SW1-Pad5)") (class "Default")
      (node (ref "SW1") (pin "5") (pinfunction "5_5") (pintype "unspecified"))
    )
    (net (code "74") (name "unconnected-(SW1-Pad6)") (class "Default")
      (node (ref "SW1") (pin "6") (pinfunction "6_6") (pintype "unspecified"))
    )
    (net (code "75") (name "unconnected-(SW2-Pad2)") (class "Default")
      (node (ref "SW2") (pin "2") (pinfunction "2_2") (pintype "unspecified"))
    )
    (net (code "76") (name "unconnected-(SW2-Pad4)") (class "Default")
      (node (ref "SW2") (pin "4") (pinfunction "4_4") (pintype "unspecified"))
    )
    (net (code "77") (name "unconnected-(U1-ALE-Pad30)") (class "Default")
      (node (ref "U1") (pin "30") (pinfunction "ALE_30") (pintype "unspecified"))
    )
    (net (code "78") (name "unconnected-(U1-PSEN#-Pad29)") (class "Default")
      (node (ref "U1") (pin "29") (pinfunction "PSEN#_29") (pintype "unspecified"))
    )
    (net (code "79") (name "unconnected-(USB1-D+-Pad3)") (class "Default")
      (node (ref "USB1") (pin "3") (pinfunction "D+_3") (pintype "unspecified"))
    )
    (net (code "80") (name "unconnected-(USB1-D--Pad2)") (class "Default")
      (node (ref "USB1") (pin "2") (pinfunction "D-_2") (pintype "unspecified"))
    )
    (net (code "81") (name "unconnected-(USB1-GND-Pad5)") (class "Default")
      (node (ref "USB1") (pin "5") (pinfunction "GND_5") (pintype "unspecified"))
    )
    (net (code "82") (name "unconnected-(USB1-GND-Pad6)") (class "Default")
      (node (ref "USB1") (pin "6") (pinfunction "GND_6") (pintype "unspecified"))
    )
  )
)
